# EIT_LAN.net
KiCad netlist of a schematic drawn in Altium Designer
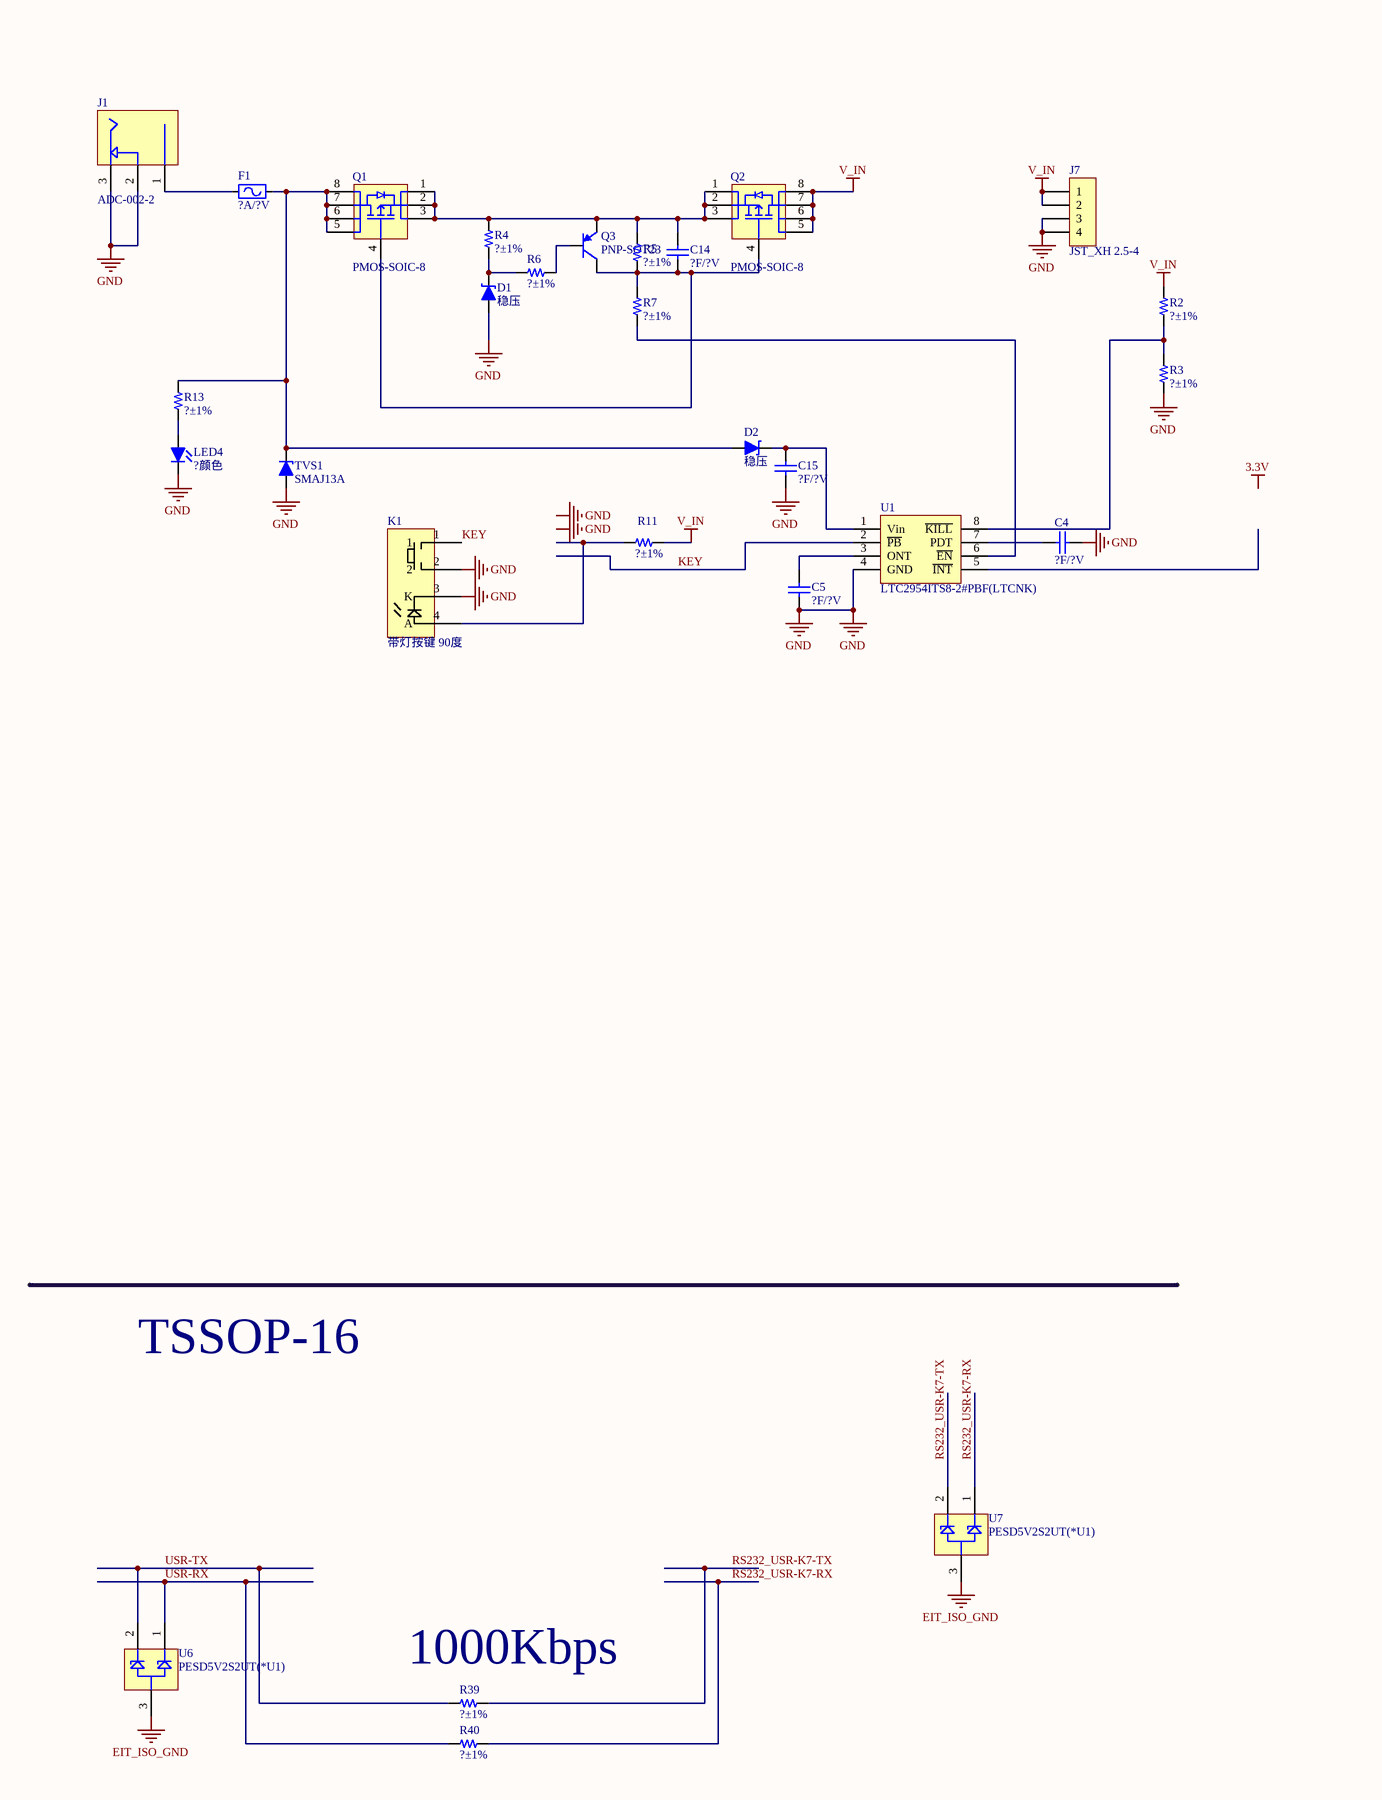
[diagram p0: EIT 串口转LAN.SchDoc, left]
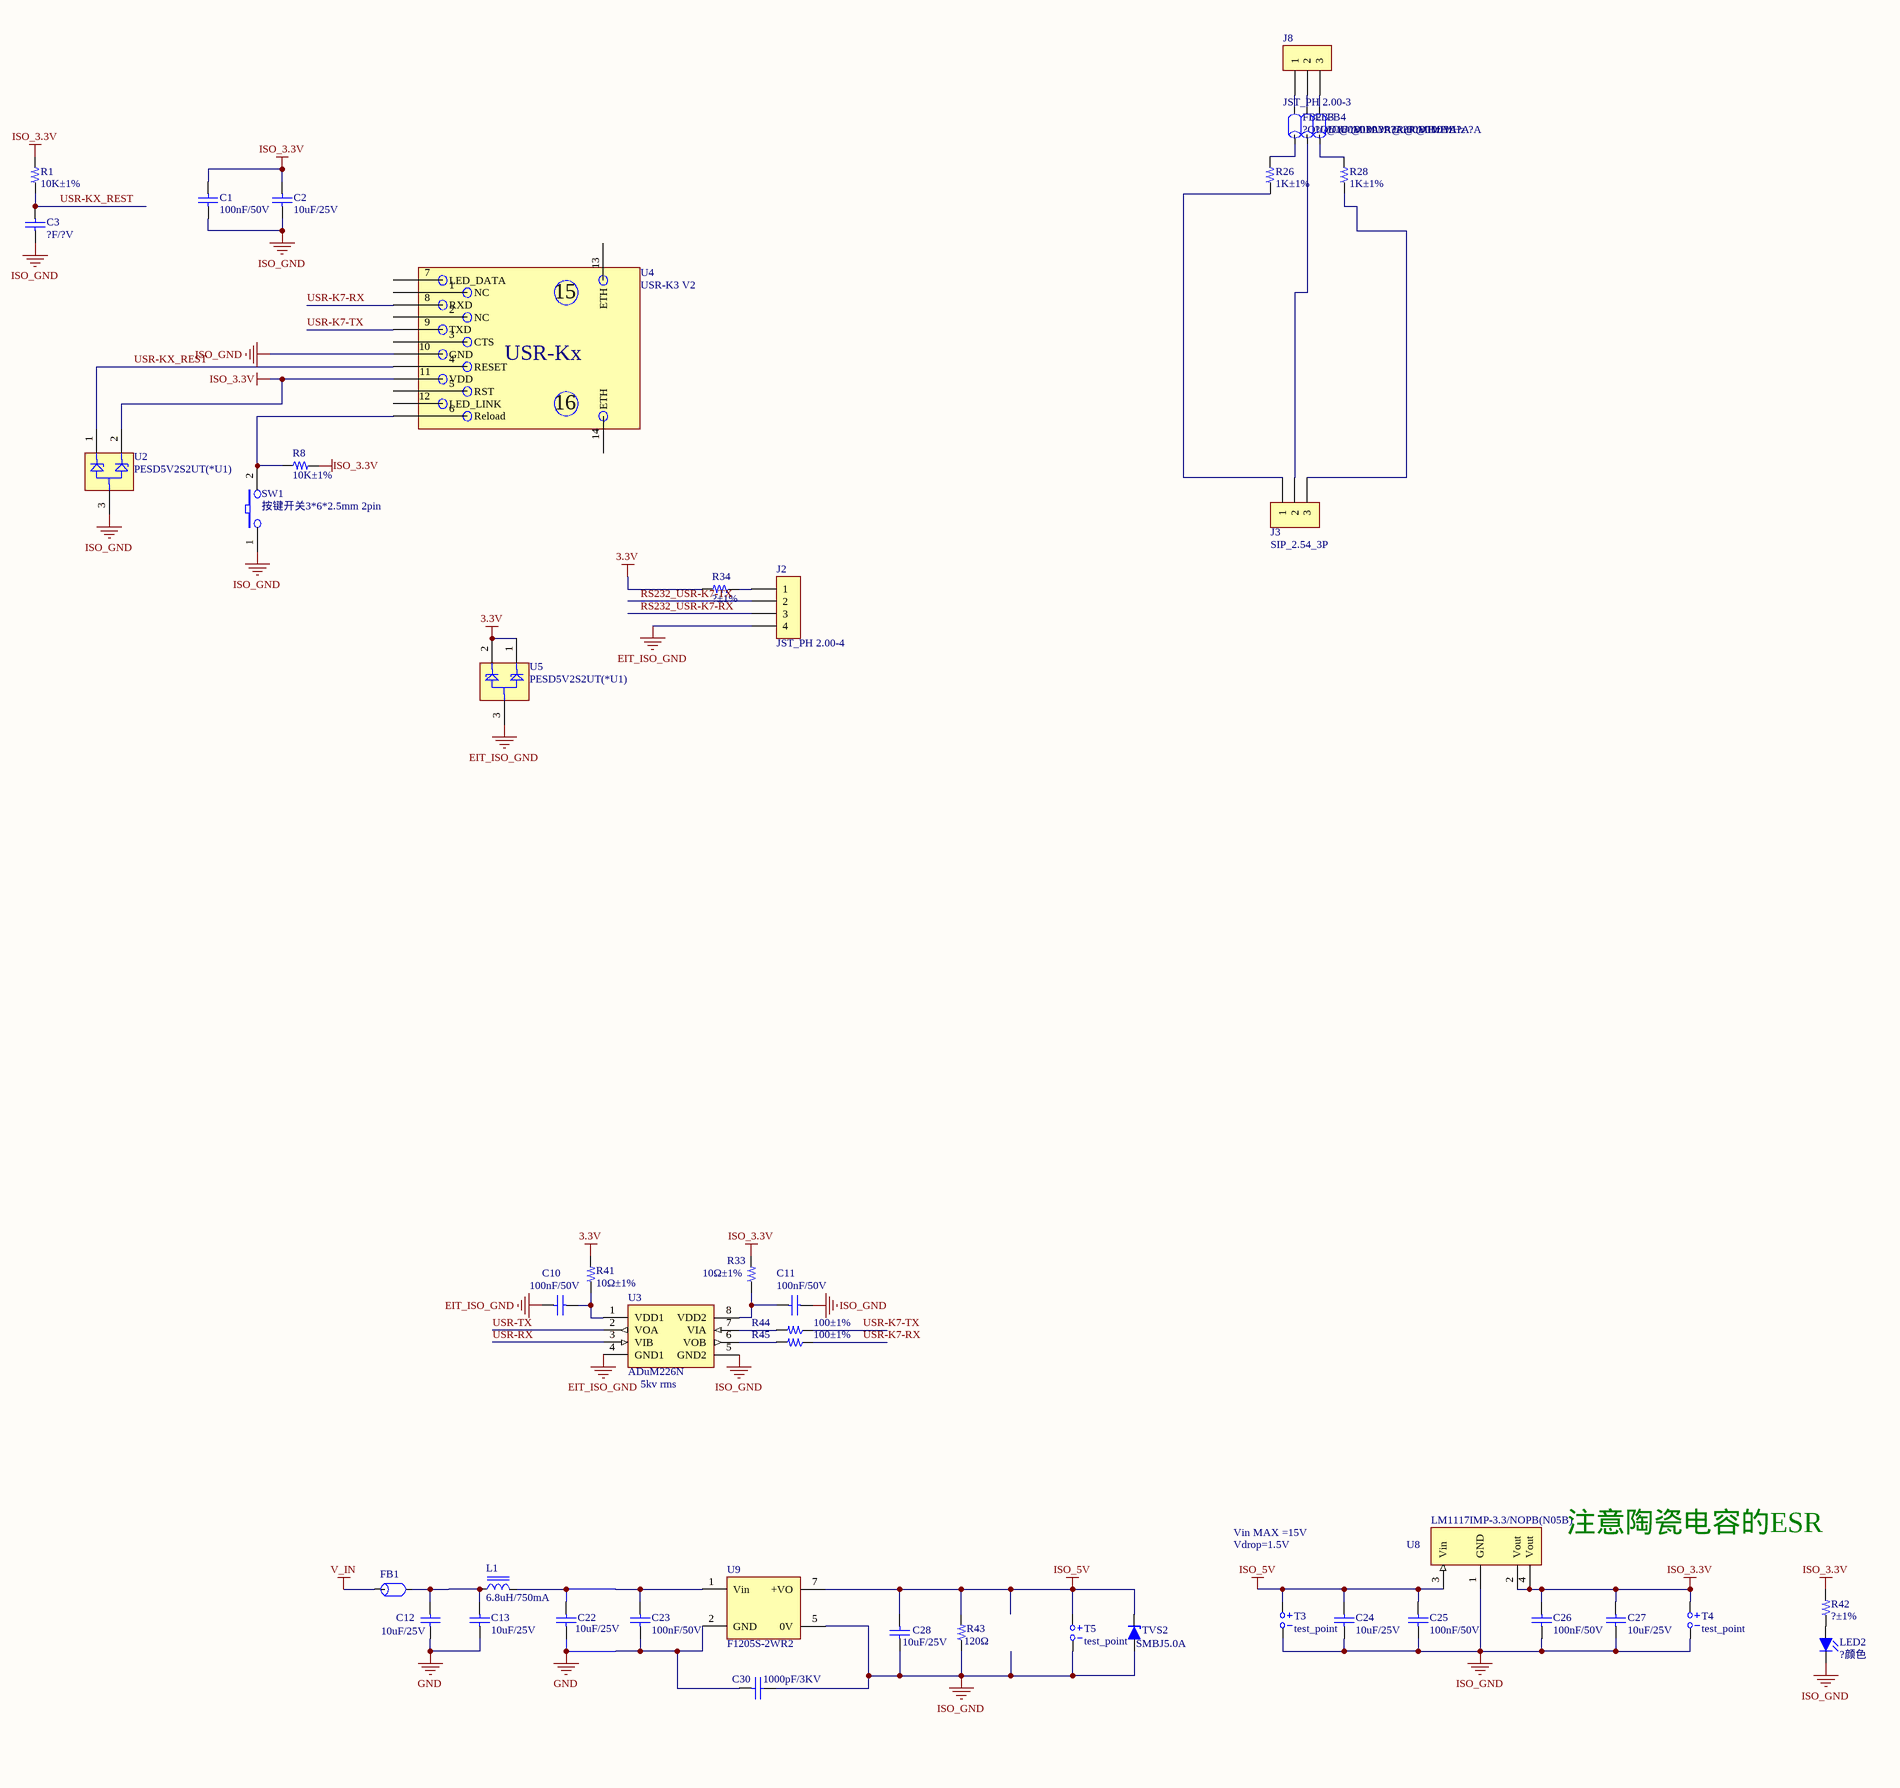
[diagram p1: EIT 串口转LAN.SchDoc, right]

(export (version "E")
  (design (tool "Eeschema 10.0.6"))
  (components
    (comp (ref "C1") (value "100nF/50V") (footprint "C-0603") (libsource (lib "Device") (part "C-0603")))
    (comp (ref "C2") (value "10uF/25V") (footprint "C-1206") (libsource (lib "Device") (part "C-1206")))
    (comp (ref "C3") (value "?F/?V") (footprint "C-0603") (libsource (lib "Device") (part "C-0603")))
    (comp (ref "C4") (value "?F/?V") (footprint "C-0805") (libsource (lib "Device") (part "C-0805")))
    (comp (ref "C5") (value "?F/?V") (footprint "C-0805") (libsource (lib "Device") (part "C-0805")))
    (comp (ref "C10") (value "100nF/50V") (footprint "C-0603") (libsource (lib "Device") (part "C-0603")))
    (comp (ref "C11") (value "100nF/50V") (footprint "C-0603") (libsource (lib "Device") (part "C-0603")))
    (comp (ref "C12") (value "10uF/25V") (footprint "C-1210") (libsource (lib "Device") (part "C-1210")))
    (comp (ref "C13") (value "10uF/25V") (footprint "C-1210") (libsource (lib "Device") (part "C-1210")))
    (comp (ref "C14") (value "?F/?V") (footprint "C-0603") (libsource (lib "Device") (part "C-0603")))
    (comp (ref "C15") (value "?F/?V") (footprint "C-0805") (libsource (lib "Device") (part "C-0805")))
    (comp (ref "C22") (value "10uF/25V") (footprint "C-1210") (libsource (lib "Device") (part "C-1210")))
    (comp (ref "C23") (value "100nF/50V") (footprint "C-0603") (libsource (lib "Device") (part "C-0603")))
    (comp (ref "C24") (value "10uF/25V") (footprint "C-1206") (libsource (lib "Device") (part "C-1206")))
    (comp (ref "C25") (value "100nF/50V") (footprint "C-0603") (libsource (lib "Device") (part "C-0603")))
    (comp (ref "C26") (value "100nF/50V") (footprint "C-0603") (libsource (lib "Device") (part "C-0603")))
    (comp (ref "C27") (value "10uF/25V") (footprint "C-1206") (libsource (lib "Device") (part "C-1206")))
    (comp (ref "C28") (value "10uF/25V") (footprint "C-1210") (libsource (lib "Device") (part "C-1210")))
    (comp (ref "C30")
      (value "1000pF/3KV")
      (footprint "HV_CAP")
      (description "品牌：VISHAY(威世)，型号：S102K43X7RR6###R , 径向引线, X7R，ROHS")
      (libsource (lib "*") (part "CAP"))
    )
    (comp (ref "D1")
      (value "稳压")
      (footprint "DO-213AB/LL34/MiniMELF")
      (libsource (lib "Device") (part "Diode-稳压-213AB/LL34/MiniMELF"))
    )
    (comp (ref "D2")
      (value "稳压")
      (footprint "DO-214AC/SMA")
      (libsource (lib "Device") (part "Diode- 稳压-214AC (SMA)"))
    )
    (comp (ref "F1")
      (value "?A/?V")
      (footprint "F-Littlefuse_154")
      (libsource (lib "others") (part "F-Littlefuse_154"))
    )
    (comp (ref "FB1")
      (value "贴片磁珠600R@100MHz,2500mA,1206")
      (footprint "FB-1206")
      (description "品牌:Wurth品牌:Wurth，型号: 742792118, Rdc=0.07ohm，size 1206,2500mA，符合ROHS。")
      (libsource (lib "Device") (part "FB-1206"))
    )
    (comp (ref "FB2")
      (value "?OU/@100M ?A?R@100MHz ?A")
      (footprint "FB-0805")
      (libsource (lib "Device") (part "FB-0805"))
    )
    (comp (ref "FB3")
      (value "?OU/@100M ?A?R@100MHz ?A")
      (footprint "FB-0805")
      (libsource (lib "Device") (part "FB-0805"))
    )
    (comp (ref "FB4")
      (value "?OU/@100M ?A?R@100MHz ?A")
      (footprint "FB-0805")
      (libsource (lib "Device") (part "FB-0805"))
    )
    (comp (ref "J1")
      (value "ADC-002-2")
      (footprint "ADC-002-2")
      (libsource (lib "connectors") (part "ADC-002-2"))
    )
    (comp (ref "J2")
      (value "JST_PH 2.00-4")
      (footprint "JST_PH 2.00-4")
      (description "品牌：JST 型号：B4B-PH-K-S，直插，间距2.00，4pin")
      (libsource (lib "connectors") (part "JST_PH 2.00-4"))
    )
    (comp (ref "J3")
      (value "SIP_2.54_3P")
      (footprint "SIP_2.54_3P")
      (libsource (lib "connectors") (part "SIP_2.54_3P"))
    )
    (comp (ref "J7")
      (value "JST_XH 2.5-4")
      (footprint "JST_XH 2.5-4")
      (description "品牌：JST 型号：B4B-XH-A，直插，间距2.5，4pin")
      (libsource (lib "connectors") (part "JST_XH 2.5-4"))
    )
    (comp (ref "J8")
      (value "JST_PH 2.00-3")
      (footprint "JST_PH 2.00-3")
      (description "品牌：JST 型号：B3B-PH-K-S，直插，间距2.00，3pin")
      (libsource (lib "connectors") (part "JST_PH 2.00-3"))
    )
    (comp (ref "K1")
      (value "带灯按键 90度")
      (footprint "带灯按键 90度")
      (libsource (lib "others") (part "POWER_BUTTON"))
    )
    (comp (ref "L1")
      (value "6.8uH/750mA")
      (footprint "L-WE-TPC Size 3816")
      (libsource (lib "Device") (part "L-WE-TPC Size 3816"))
    )
    (comp (ref "LED2") (value "?颜色") (footprint "LED-0805") (libsource (lib "Device") (part "LED-0805")))
    (comp (ref "LED4") (value "?颜色") (footprint "LED-0805") (libsource (lib "Device") (part "LED-0805")))
    (comp (ref "Q1")
      (value "PMOS-SOIC-8")
      (footprint "SOIC-8(4.90*3.9)")
      (description "品牌：型号：")
      (libsource (lib "") (part "PMOS-SOIC-8_1"))
    )
    (comp (ref "Q2")
      (value "PMOS-SOIC-8")
      (footprint "SOIC-8(4.90*3.9)")
      (description "品牌：型号：")
      (libsource (lib "Device") (part "PMOS-SOIC-8"))
    )
    (comp (ref "Q3")
      (value "PNP-SOT23")
      (footprint "SOT23-3")
      (description "品牌：型号：")
      (libsource (lib "Device") (part "PNP-SOT23"))
    )
    (comp (ref "R1") (value "10K±1%") (footprint "R-0805") (libsource (lib "Device") (part "R-0805")))
    (comp (ref "R2") (value "?±1%") (footprint "R-0603") (libsource (lib "Device") (part "R-0603")))
    (comp (ref "R3") (value "?±1%") (footprint "R-0603") (libsource (lib "Device") (part "R-0603")))
    (comp (ref "R4") (value "?±1%") (footprint "R-0603") (libsource (lib "Device") (part "R-0603")))
    (comp (ref "R5") (value "?±1%") (footprint "R-0603") (libsource (lib "Device") (part "R-0603")))
    (comp (ref "R6") (value "?±1%") (footprint "R-0603") (libsource (lib "Device") (part "R-0603")))
    (comp (ref "R7") (value "?±1%") (footprint "R-0603") (libsource (lib "Device") (part "R-0603")))
    (comp (ref "R8") (value "10K±1%") (footprint "R-0805") (libsource (lib "Device") (part "R-0805")))
    (comp (ref "R11") (value "?±1%") (footprint "R-1206") (libsource (lib "Device") (part "R-1206")))
    (comp (ref "R13") (value "?±1%") (footprint "R-0603") (libsource (lib "Device") (part "R-0603")))
    (comp (ref "R26") (value "1K±1%") (footprint "R-0603") (libsource (lib "Device") (part "R-0603")))
    (comp (ref "R28") (value "1K±1%") (footprint "R-0603") (libsource (lib "Device") (part "R-0603")))
    (comp (ref "R33") (value "10Ω±1%") (footprint "R-0805") (libsource (lib "Device") (part "R-0805")))
    (comp (ref "R34") (value "?±1%") (footprint "R-0805") (libsource (lib "Device") (part "R-0805")))
    (comp (ref "R39") (value "?±1%") (footprint "R-0603") (libsource (lib "Device") (part "R-0603")))
    (comp (ref "R40") (value "?±1%") (footprint "R-0603") (libsource (lib "Device") (part "R-0603")))
    (comp (ref "R41") (value "10Ω±1%") (footprint "R-0805") (libsource (lib "Device") (part "R-0805")))
    (comp (ref "R42") (value "?±1%") (footprint "R-0603") (libsource (lib "Device") (part "R-0603")))
    (comp (ref "R43")
      (value "120Ω")
      (footprint "R-2512")
      (description "国巨RC2512FK-073R")
      (libsource (lib "电阻") (part "3Ω_1"))
    )
    (comp (ref "R44") (value "100±1%") (footprint "R-0603") (libsource (lib "Device") (part "R-0603")))
    (comp (ref "R45") (value "100±1%") (footprint "R-0603") (libsource (lib "Device") (part "R-0603")))
    (comp (ref "SW1")
      (value "按键开关3*6*2.5mm 2pin")
      (footprint "按键开关3*6*2.5mm 2pin")
      (libsource (lib "others") (part "按键开关3*6*2.5mm 2pin"))
    )
    (comp (ref "T3") (value "test_point") (footprint "TP-DIP-2") (libsource (lib "others") (part "TP-DIP-2")))
    (comp (ref "T4") (value "test_point") (footprint "TP-DIP-2") (libsource (lib "others") (part "TP-DIP-2")))
    (comp (ref "T5") (value "test_point") (footprint "TP-DIP-2") (libsource (lib "others") (part "TP-DIP-2")))
    (comp (ref "TVS1")
      (value "SMAJ13A")
      (footprint "DO-214AC/SMA")
      (libsource (lib "Device") (part "TVS-Diode-214AC/SMA"))
    )
    (comp (ref "TVS2")
      (value "SMBJ5.0A")
      (footprint "DO-214AA/SMB")
      (libsource (lib "Device") (part "TVS-Diode-214AA/SMB"))
    )
    (comp (ref "U1")
      (value "LTC2954ITS8-2#PBF(LTCNK)")
      (footprint "SOT23-8")
      (description "Linear,LTC2954ITS8-2#PBF,TSOT-23,–40~+85°C,")
      (libsource (lib "IC") (part "LTC2954ITS8-2#PBF"))
    )
    (comp (ref "U2")
      (value "PESD5V2S2UT(*U1)")
      (footprint "SOT23-3")
      (description "品牌：NXP，型号：PESD5V2S2UT，SOT23-3，ROHS")
      (libsource (lib "") (part "PESD5V2S2UT_1"))
    )
    (comp (ref "U3")
      (value "ADuM226N")
      (footprint "SOIC-8(Wide Body)")
      (description "品牌：ADI，型号：ADuM226N0BRIZ,SOIC-8,-40~+105°C,ROHS")
      (libsource (lib "IC") (part "ADuM226N"))
    )
    (comp (ref "U4") (value "USR-K3 V2") (libsource (lib "USR-Kx") (part "USR-K3 V2")))
    (comp (ref "U5")
      (value "PESD5V2S2UT(*U1)")
      (footprint "SOT23-3")
      (description "品牌：NXP，型号：PESD5V2S2UT，SOT23-3，ROHS")
      (libsource (lib "IC") (part "PESD5V2S2UT"))
    )
    (comp (ref "U6")
      (value "PESD5V2S2UT(*U1)")
      (footprint "SOT23-3")
      (description "品牌：NXP，型号：PESD5V2S2UT，SOT23-3，ROHS")
      (libsource (lib "IC") (part "PESD5V2S2UT"))
    )
    (comp (ref "U7")
      (value "PESD5V2S2UT(*U1)")
      (footprint "SOT23-3")
      (description "品牌：NXP，型号：PESD5V2S2UT，SOT23-3，ROHS")
      (libsource (lib "IC") (part "PESD5V2S2UT"))
    )
    (comp (ref "U8")
      (value "LM1117IMP-3.3/NOPB(N05B)")
      (footprint "SOT223")
      (description "品牌：TI，型号：LM1117IMP-3.3/NOPB，800-mA Low-Dropout，SOT223，-40~+ 125°C，ROHS")
      (libsource (lib "IC") (part "LM1117IMP-3.3/NOPB"))
    )
    (comp (ref "U9")
      (value "F1205S-2WR2")
      (footprint "F_S-2WR2")
      (description "品牌：金升阳，型号：，3000VDC隔离，输出2W")
      (libsource (lib "others") (part "F_S-2WR2"))
    )
  )
  (nets
    (net (code "1") (name "/KEY") (class "Default")
      (node (ref "K1") (pin "1") (pinfunction "1_1") (pintype "passive"))
      (node (ref "U1") (pin "2") (pinfunction "~{PB}_2") (pintype "passive"))
    )
    (net (code "2") (name "/RS232_USR-K7-RX") (class "Default")
      (node (ref "J2") (pin "3") (pinfunction "3_3") (pintype "passive"))
      (node (ref "R40") (pin "2") (pinfunction "2_2") (pintype "passive"))
      (node (ref "U7") (pin "1") (pinfunction "1_1") (pintype "passive"))
    )
    (net (code "3") (name "/RS232_USR-K7-TX") (class "Default")
      (node (ref "J2") (pin "2") (pinfunction "2_2") (pintype "passive"))
      (node (ref "R39") (pin "2") (pinfunction "2_2") (pintype "passive"))
      (node (ref "U7") (pin "2") (pinfunction "2_2") (pintype "passive"))
    )
    (net (code "4") (name "/USR-K7-RX") (class "Default")
      (node (ref "R45") (pin "1") (pinfunction "1_1") (pintype "passive"))
      (node (ref "U4") (pin "8") (pinfunction "RXD_8") (pintype "passive"))
    )
    (net (code "5") (name "/USR-K7-TX") (class "Default")
      (node (ref "R44") (pin "1") (pinfunction "1_1") (pintype "passive"))
      (node (ref "U4") (pin "9") (pinfunction "TXD_9") (pintype "passive"))
    )
    (net (code "6") (name "/USR-KX_REST") (class "Default")
      (node (ref "C3") (pin "1") (pinfunction "1_1") (pintype "passive"))
      (node (ref "R1") (pin "1") (pinfunction "1_1") (pintype "passive"))
      (node (ref "U2") (pin "1") (pinfunction "1_1") (pintype "passive"))
      (node (ref "U4") (pin "4") (pinfunction "RESET_4") (pintype "passive"))
    )
    (net (code "7") (name "/USR-RX") (class "Default")
      (node (ref "R40") (pin "1") (pinfunction "1_1") (pintype "passive"))
      (node (ref "U3") (pin "3") (pinfunction "VIB_3") (pintype "input"))
      (node (ref "U6") (pin "1") (pinfunction "1_1") (pintype "passive"))
    )
    (net (code "8") (name "/USR-TX") (class "Default")
      (node (ref "R39") (pin "1") (pinfunction "1_1") (pintype "passive"))
      (node (ref "U3") (pin "2") (pinfunction "VOA_2") (pintype "output"))
      (node (ref "U6") (pin "2") (pinfunction "2_2") (pintype "passive"))
    )
    (net (code "9") (name "3.3V") (class "Default")
      (node (ref "R34") (pin "1") (pinfunction "1_1") (pintype "passive"))
      (node (ref "R41") (pin "2") (pinfunction "2_2") (pintype "passive"))
      (node (ref "U5") (pin "1") (pinfunction "1_1") (pintype "passive"))
      (node (ref "U5") (pin "2") (pinfunction "2_2") (pintype "passive"))
    )
    (net (code "10") (name "EIT_ISO_GND") (class "Default")
      (node (ref "C10") (pin "2") (pinfunction "2_2") (pintype "passive"))
      (node (ref "J2") (pin "4") (pinfunction "4_4") (pintype "passive"))
      (node (ref "U3") (pin "4") (pinfunction "GND1_4") (pintype "passive"))
      (node (ref "U5") (pin "3") (pinfunction "3_3") (pintype "passive"))
      (node (ref "U6") (pin "3") (pinfunction "3_3") (pintype "passive"))
      (node (ref "U7") (pin "3") (pinfunction "3_3") (pintype "passive"))
    )
    (net (code "11") (name "GND") (class "Default")
      (node (ref "C12") (pin "1") (pinfunction "1_1") (pintype "passive"))
      (node (ref "C13") (pin "1") (pinfunction "1_1") (pintype "passive"))
      (node (ref "C15") (pin "1") (pinfunction "1_1") (pintype "passive"))
      (node (ref "C22") (pin "1") (pinfunction "1_1") (pintype "passive"))
      (node (ref "C23") (pin "2") (pinfunction "2_2") (pintype "passive"))
      (node (ref "C30") (pin "1") (pinfunction "1_1") (pintype "passive"))
      (node (ref "C4") (pin "2") (pinfunction "2_2") (pintype "passive"))
      (node (ref "C5") (pin "1") (pinfunction "1_1") (pintype "passive"))
      (node (ref "D1") (pin "A") (pinfunction "A_A") (pintype "passive"))
      (node (ref "J1") (pin "2") (pinfunction "2_2") (pintype "passive"))
      (node (ref "J1") (pin "3") (pinfunction "3_3") (pintype "passive"))
      (node (ref "J7") (pin "3") (pinfunction "3_3") (pintype "passive"))
      (node (ref "J7") (pin "4") (pinfunction "4_4") (pintype "passive"))
      (node (ref "K1") (pin "2") (pinfunction "2_2") (pintype "passive"))
      (node (ref "K1") (pin "3") (pinfunction "K_3") (pintype "passive"))
      (node (ref "LED4") (pin "K") (pinfunction "K_K") (pintype "passive"))
      (node (ref "R3") (pin "1") (pinfunction "1_1") (pintype "passive"))
      (node (ref "TVS1") (pin "A") (pinfunction "A_A") (pintype "passive"))
      (node (ref "U1") (pin "4") (pinfunction "GND_4") (pintype "passive"))
      (node (ref "U9") (pin "2") (pinfunction "GND_2") (pintype "passive"))
    )
    (net (code "12") (name "ISO_3.3V") (class "Default")
      (node (ref "C1") (pin "2") (pinfunction "2_2") (pintype "passive"))
      (node (ref "C2") (pin "2") (pinfunction "2_2") (pintype "passive"))
      (node (ref "C26") (pin "2") (pinfunction "2_2") (pintype "passive"))
      (node (ref "C27") (pin "2") (pinfunction "2_2") (pintype "passive"))
      (node (ref "R1") (pin "2") (pinfunction "2_2") (pintype "passive"))
      (node (ref "R33") (pin "2") (pinfunction "2_2") (pintype "passive"))
      (node (ref "R42") (pin "2") (pinfunction "2_2") (pintype "passive"))
      (node (ref "R8") (pin "2") (pinfunction "2_2") (pintype "passive"))
      (node (ref "T4") (pin "1") (pinfunction "+_1") (pintype "passive"))
      (node (ref "U2") (pin "2") (pinfunction "2_2") (pintype "passive"))
      (node (ref "U4") (pin "11") (pinfunction "VDD_11") (pintype "passive"))
      (node (ref "U8") (pin "2") (pinfunction "Vout_2") (pintype "passive"))
      (node (ref "U8") (pin "4") (pinfunction "Vout_4") (pintype "passive"))
    )
    (net (code "13") (name "ISO_5V") (class "Default")
      (node (ref "C24") (pin "2") (pinfunction "2_2") (pintype "passive"))
      (node (ref "C25") (pin "2") (pinfunction "2_2") (pintype "passive"))
      (node (ref "C28") (pin "2") (pinfunction "2_2") (pintype "passive"))
      (node (ref "R43") (pin "2") (pinfunction "BOT_2") (pintype "passive"))
      (node (ref "T3") (pin "1") (pinfunction "+_1") (pintype "passive"))
      (node (ref "T5") (pin "1") (pinfunction "+_1") (pintype "passive"))
      (node (ref "TVS2") (pin "K") (pinfunction "K_K") (pintype "passive"))
      (node (ref "U8") (pin "3") (pinfunction "Vin_3") (pintype "input"))
      (node (ref "U9") (pin "7") (pinfunction "+VO_7") (pintype "passive"))
    )
    (net (code "14") (name "ISO_GND") (class "Default")
      (node (ref "C1") (pin "1") (pinfunction "1_1") (pintype "passive"))
      (node (ref "C11") (pin "1") (pinfunction "1_1") (pintype "passive"))
      (node (ref "C2") (pin "1") (pinfunction "1_1") (pintype "passive"))
      (node (ref "C24") (pin "1") (pinfunction "1_1") (pintype "passive"))
      (node (ref "C25") (pin "1") (pinfunction "1_1") (pintype "passive"))
      (node (ref "C26") (pin "1") (pinfunction "1_1") (pintype "passive"))
      (node (ref "C27") (pin "1") (pinfunction "1_1") (pintype "passive"))
      (node (ref "C28") (pin "1") (pinfunction "1_1") (pintype "passive"))
      (node (ref "C3") (pin "2") (pinfunction "2_2") (pintype "passive"))
      (node (ref "C30") (pin "2") (pinfunction "2_2") (pintype "passive"))
      (node (ref "LED2") (pin "K") (pinfunction "K_K") (pintype "passive"))
      (node (ref "R43") (pin "1") (pinfunction "TOP_1") (pintype "passive"))
      (node (ref "SW1") (pin "1") (pinfunction "1_1") (pintype "passive"))
      (node (ref "T3") (pin "2") (pinfunction "-_2") (pintype "passive"))
      (node (ref "T4") (pin "2") (pinfunction "-_2") (pintype "passive"))
      (node (ref "T5") (pin "2") (pinfunction "-_2") (pintype "passive"))
      (node (ref "TVS2") (pin "A") (pinfunction "A_A") (pintype "passive"))
      (node (ref "U2") (pin "3") (pinfunction "3_3") (pintype "passive"))
      (node (ref "U3") (pin "5") (pinfunction "GND2_5") (pintype "power_in"))
      (node (ref "U4") (pin "10") (pinfunction "GND_10") (pintype "passive"))
      (node (ref "U8") (pin "1") (pinfunction "GND_1") (pintype "power_in"))
      (node (ref "U9") (pin "5") (pinfunction "0V_5") (pintype "passive"))
    )
    (net (code "15") (name "Net-(C12-Pad2)") (class "Default")
      (node (ref "C12") (pin "2") (pinfunction "2_2") (pintype "passive"))
      (node (ref "C13") (pin "2") (pinfunction "2_2") (pintype "passive"))
      (node (ref "FB1") (pin "2") (pinfunction "2_2") (pintype "passive"))
      (node (ref "L1") (pin "1") (pinfunction "1_1") (pintype "passive"))
    )
    (net (code "16") (name "Net-(D1-PadK)") (class "Default")
      (node (ref "D1") (pin "K") (pinfunction "K_K") (pintype "passive"))
      (node (ref "R4") (pin "1") (pinfunction "1_1") (pintype "passive"))
      (node (ref "R6") (pin "2") (pinfunction "2_2") (pintype "passive"))
    )
    (net (code "17") (name "Net-(D2-PadA)") (class "Default")
      (node (ref "D2") (pin "A") (pinfunction "A_A") (pintype "passive"))
      (node (ref "F1") (pin "1") (pinfunction "1_1") (pintype "passive"))
      (node (ref "Q1") (pin "5") (pinfunction "D_5") (pintype "passive"))
      (node (ref "Q1") (pin "6") (pinfunction "D_6") (pintype "passive"))
      (node (ref "Q1") (pin "7") (pinfunction "D_7") (pintype "passive"))
      (node (ref "Q1") (pin "8") (pinfunction "D_8") (pintype "passive"))
      (node (ref "R13") (pin "2") (pinfunction "2_2") (pintype "passive"))
      (node (ref "TVS1") (pin "K") (pinfunction "K_K") (pintype "passive"))
    )
    (net (code "18") (name "Net-(F1-Pad2)") (class "Default")
      (node (ref "F1") (pin "2") (pinfunction "2_2") (pintype "passive"))
      (node (ref "J1") (pin "1") (pinfunction "1_1") (pintype "passive"))
    )
    (net (code "19") (name "Net-(FB2-Pad1)") (class "Default")
      (node (ref "FB2") (pin "1") (pinfunction "1_1") (pintype "passive"))
      (node (ref "R26") (pin "2") (pinfunction "2_2") (pintype "passive"))
    )
    (net (code "20") (name "Net-(FB2-Pad2)") (class "Default")
      (node (ref "FB2") (pin "2") (pinfunction "2_2") (pintype "passive"))
      (node (ref "J8") (pin "1") (pinfunction "1_1") (pintype "passive"))
    )
    (net (code "21") (name "Net-(FB3-Pad1)") (class "Default")
      (node (ref "FB3") (pin "1") (pinfunction "1_1") (pintype "passive"))
      (node (ref "J3") (pin "2") (pinfunction "2_2") (pintype "passive"))
    )
    (net (code "22") (name "Net-(FB3-Pad2)") (class "Default")
      (node (ref "FB3") (pin "2") (pinfunction "2_2") (pintype "passive"))
      (node (ref "J8") (pin "2") (pinfunction "2_2") (pintype "passive"))
    )
    (net (code "23") (name "Net-(FB4-Pad1)") (class "Default")
      (node (ref "FB4") (pin "1") (pinfunction "1_1") (pintype "passive"))
      (node (ref "R28") (pin "2") (pinfunction "2_2") (pintype "passive"))
    )
    (net (code "24") (name "Net-(FB4-Pad2)") (class "Default")
      (node (ref "FB4") (pin "2") (pinfunction "2_2") (pintype "passive"))
      (node (ref "J8") (pin "3") (pinfunction "3_3") (pintype "passive"))
    )
    (net (code "25") (name "Net-(J2-Pad1)") (class "Default")
      (node (ref "J2") (pin "1") (pinfunction "1_1") (pintype "passive"))
      (node (ref "R34") (pin "2") (pinfunction "2_2") (pintype "passive"))
    )
    (net (code "26") (name "Net-(J3-Pad1)") (class "Default")
      (node (ref "J3") (pin "1") (pinfunction "1_1") (pintype "passive"))
      (node (ref "R26") (pin "1") (pinfunction "1_1") (pintype "passive"))
    )
    (net (code "27") (name "Net-(J3-Pad3)") (class "Default")
      (node (ref "J3") (pin "3") (pinfunction "3_3") (pintype "passive"))
      (node (ref "R28") (pin "1") (pinfunction "1_1") (pintype "passive"))
    )
    (net (code "28") (name "Net-(K1-A)") (class "Default")
      (node (ref "K1") (pin "4") (pinfunction "A_4") (pintype "passive"))
      (node (ref "R11") (pin "1") (pinfunction "1_1") (pintype "passive"))
    )
    (net (code "29") (name "Net-(LED2-PadA)") (class "Default")
      (node (ref "LED2") (pin "A") (pinfunction "A_A") (pintype "passive"))
      (node (ref "R42") (pin "1") (pinfunction "1_1") (pintype "passive"))
    )
    (net (code "30") (name "Net-(LED4-PadA)") (class "Default")
      (node (ref "LED4") (pin "A") (pinfunction "A_A") (pintype "passive"))
      (node (ref "R13") (pin "1") (pinfunction "1_1") (pintype "passive"))
    )
    (net (code "31") (name "Net-(Q1-G)") (class "Default")
      (node (ref "C14") (pin "2") (pinfunction "2_2") (pintype "passive"))
      (node (ref "Q1") (pin "4") (pinfunction "G_4") (pintype "passive"))
      (node (ref "Q2") (pin "4") (pinfunction "G_4") (pintype "passive"))
      (node (ref "Q3") (pin "3") (pinfunction "C_3") (pintype "passive"))
      (node (ref "R5") (pin "1") (pinfunction "1_1") (pintype "passive"))
      (node (ref "R7") (pin "2") (pinfunction "2_2") (pintype "passive"))
    )
    (net (code "32") (name "Net-(Q3-B)") (class "Default")
      (node (ref "Q3") (pin "1") (pinfunction "B_1") (pintype "passive"))
      (node (ref "R6") (pin "1") (pinfunction "1_1") (pintype "passive"))
    )
    (net (code "33") (name "Net-(Q3-E)") (class "Default")
      (node (ref "C14") (pin "1") (pinfunction "1_1") (pintype "passive"))
      (node (ref "Q1") (pin "1") (pinfunction "S_1") (pintype "passive"))
      (node (ref "Q1") (pin "2") (pinfunction "S_2") (pintype "passive"))
      (node (ref "Q1") (pin "3") (pinfunction "S_3") (pintype "passive"))
      (node (ref "Q2") (pin "1") (pinfunction "S_1") (pintype "passive"))
      (node (ref "Q2") (pin "2") (pinfunction "S_2") (pintype "passive"))
      (node (ref "Q2") (pin "3") (pinfunction "S_3") (pintype "passive"))
      (node (ref "Q3") (pin "2") (pinfunction "E_2") (pintype "passive"))
      (node (ref "R4") (pin "2") (pinfunction "2_2") (pintype "passive"))
      (node (ref "R5") (pin "2") (pinfunction "2_2") (pintype "passive"))
    )
    (net (code "34") (name "Net-(U1-ONT)") (class "Default")
      (node (ref "C5") (pin "2") (pinfunction "2_2") (pintype "passive"))
      (node (ref "U1") (pin "3") (pinfunction "ONT_3") (pintype "passive"))
    )
    (net (code "35") (name "Net-(U1-PDT)") (class "Default")
      (node (ref "C4") (pin "1") (pinfunction "1_1") (pintype "passive"))
      (node (ref "U1") (pin "7") (pinfunction "PDT_7") (pintype "passive"))
    )
    (net (code "36") (name "Net-(U1-Vin)") (class "Default")
      (node (ref "C15") (pin "2") (pinfunction "2_2") (pintype "passive"))
      (node (ref "D2") (pin "K") (pinfunction "K_K") (pintype "passive"))
      (node (ref "U1") (pin "1") (pinfunction "Vin_1") (pintype "passive"))
    )
    (net (code "37") (name "Net-(U1-~{EN})") (class "Default")
      (node (ref "R7") (pin "1") (pinfunction "1_1") (pintype "passive"))
      (node (ref "U1") (pin "6") (pinfunction "~{EN}_6") (pintype "passive"))
    )
    (net (code "38") (name "Net-(U1-~{KILL})") (class "Default")
      (node (ref "R2") (pin "1") (pinfunction "1_1") (pintype "passive"))
      (node (ref "R3") (pin "2") (pinfunction "2_2") (pintype "passive"))
      (node (ref "U1") (pin "8") (pinfunction "~{KILL}_8") (pintype "passive"))
    )
    (net (code "39") (name "Net-(U3-VDD1)") (class "Default")
      (node (ref "C10") (pin "1") (pinfunction "1_1") (pintype "passive"))
      (node (ref "R41") (pin "1") (pinfunction "1_1") (pintype "passive"))
      (node (ref "U3") (pin "1") (pinfunction "VDD1_1") (pintype "power_in"))
    )
    (net (code "40") (name "Net-(U3-VDD2)") (class "Default")
      (node (ref "C11") (pin "2") (pinfunction "2_2") (pintype "passive"))
      (node (ref "R33") (pin "1") (pinfunction "1_1") (pintype "passive"))
      (node (ref "U3") (pin "8") (pinfunction "VDD2_8") (pintype "power_in"))
    )
    (net (code "41") (name "Net-(U3-VIA)") (class "Default")
      (node (ref "R44") (pin "2") (pinfunction "2_2") (pintype "passive"))
      (node (ref "U3") (pin "7") (pinfunction "VIA_7") (pintype "input"))
    )
    (net (code "42") (name "Net-(U3-VOB)") (class "Default")
      (node (ref "R45") (pin "2") (pinfunction "2_2") (pintype "passive"))
      (node (ref "U3") (pin "6") (pinfunction "VOB_6") (pintype "output"))
    )
    (net (code "43") (name "Net-(U4-Reload)") (class "Default")
      (node (ref "R8") (pin "1") (pinfunction "1_1") (pintype "passive"))
      (node (ref "SW1") (pin "2") (pinfunction "2_2") (pintype "passive"))
      (node (ref "U4") (pin "6") (pinfunction "Reload_6") (pintype "passive"))
    )
    (net (code "44") (name "Net-(U9-Vin)") (class "Default")
      (node (ref "C22") (pin "2") (pinfunction "2_2") (pintype "passive"))
      (node (ref "C23") (pin "1") (pinfunction "1_1") (pintype "passive"))
      (node (ref "L1") (pin "2") (pinfunction "2_2") (pintype "passive"))
      (node (ref "U9") (pin "1") (pinfunction "Vin_1") (pintype "passive"))
    )
    (net (code "45") (name "V_IN") (class "Default")
      (node (ref "FB1") (pin "1") (pinfunction "1_1") (pintype "passive"))
      (node (ref "J7") (pin "1") (pinfunction "1_1") (pintype "passive"))
      (node (ref "J7") (pin "2") (pinfunction "2_2") (pintype "passive"))
      (node (ref "Q2") (pin "5") (pinfunction "D_5") (pintype "passive"))
      (node (ref "Q2") (pin "6") (pinfunction "D_6") (pintype "passive"))
      (node (ref "Q2") (pin "7") (pinfunction "D_7") (pintype "passive"))
      (node (ref "Q2") (pin "8") (pinfunction "D_8") (pintype "passive"))
      (node (ref "R11") (pin "2") (pinfunction "2_2") (pintype "passive"))
      (node (ref "R2") (pin "2") (pinfunction "2_2") (pintype "passive"))
    )
    (net (code "46") (name "unconnected-(U1-~{INT}-Pad5)") (class "Default")
      (node (ref "U1") (pin "5") (pinfunction "~{INT}_5") (pintype "passive"))
    )
    (net (code "47") (name "unconnected-(U4-CTS-Pad3)") (class "Default")
      (node (ref "U4") (pin "3") (pinfunction "CTS_3") (pintype "passive"))
    )
    (net (code "48") (name "unconnected-(U4-ETH-Pad13)") (class "Default")
      (node (ref "U4") (pin "13") (pinfunction "ETH_13") (pintype "passive"))
    )
    (net (code "49") (name "unconnected-(U4-ETH-Pad14)") (class "Default")
      (node (ref "U4") (pin "14") (pinfunction "ETH_14") (pintype "passive"))
    )
    (net (code "50") (name "unconnected-(U4-LED_DATA-Pad7)") (class "Default")
      (node (ref "U4") (pin "7") (pinfunction "LED_DATA_7") (pintype "passive"))
    )
    (net (code "51") (name "unconnected-(U4-LED_LINK-Pad12)") (class "Default")
      (node (ref "U4") (pin "12") (pinfunction "LED_LINK_12") (pintype "passive"))
    )
    (net (code "52") (name "unconnected-(U4-NC-Pad1)") (class "Default")
      (node (ref "U4") (pin "1") (pinfunction "NC_1") (pintype "passive"))
    )
    (net (code "53") (name "unconnected-(U4-NC-Pad2)") (class "Default")
      (node (ref "U4") (pin "2") (pinfunction "NC_2") (pintype "passive"))
    )
    (net (code "54") (name "unconnected-(U4-RST-Pad5)") (class "Default")
      (node (ref "U4") (pin "5") (pinfunction "RST_5") (pintype "passive"))
    )
  )
)
